# FormulaCore.net
KiCad netlist of a schematic drawn in EAGLE
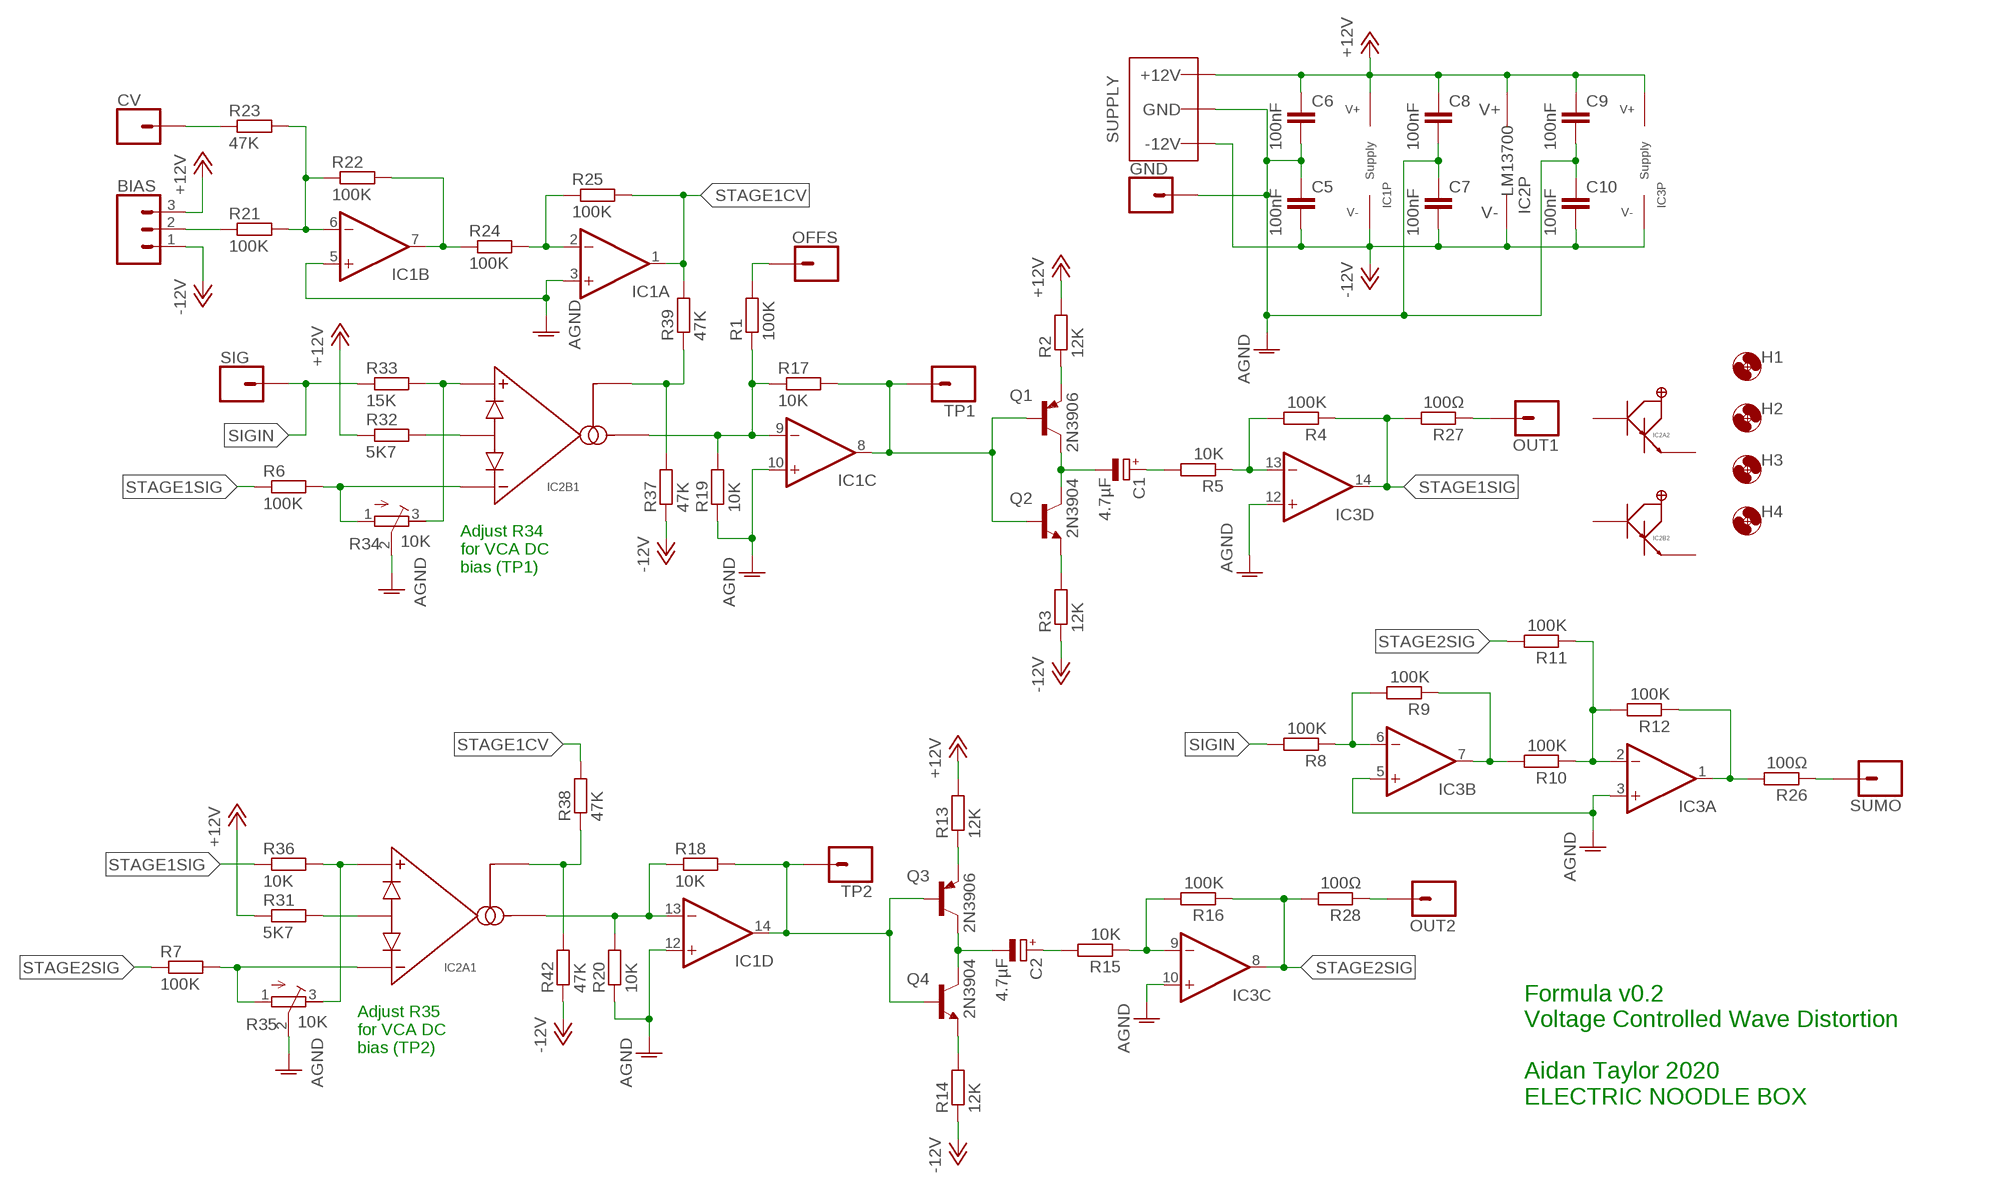
[diagram p0: schematic, sheet 1]

(export (version "E")
  (design (tool "Eeschema 10.0.6"))
  (components
    (comp (ref "BIAS")
      (value "3XWIREPAD")
      (footprint "eagle-import:1X03")
      (libsource (lib "eagle-import") (part "3XWIREPAD"))
    )
    (comp (ref "C1")
      (value "4.7µF")
      (footprint "eagle-import:E2,5-5")
      (libsource (lib "eagle-import") (part "CPOL-EUE2.5-5"))
    )
    (comp (ref "C2")
      (value "4.7µF")
      (footprint "eagle-import:E2,5-5")
      (libsource (lib "eagle-import") (part "CPOL-EUE2.5-5"))
    )
    (comp (ref "C5")
      (value "100nF")
      (footprint "eagle-import:C050-025X075")
      (libsource (lib "eagle-import") (part "C-EU050-025X075"))
    )
    (comp (ref "C6")
      (value "100nF")
      (footprint "eagle-import:C050-025X075")
      (libsource (lib "eagle-import") (part "C-EU050-025X075"))
    )
    (comp (ref "C7")
      (value "100nF")
      (footprint "eagle-import:C050-025X075")
      (libsource (lib "eagle-import") (part "C-EU050-025X075"))
    )
    (comp (ref "C8")
      (value "100nF")
      (footprint "eagle-import:C050-025X075")
      (libsource (lib "eagle-import") (part "C-EU050-025X075"))
    )
    (comp (ref "C9")
      (value "100nF")
      (footprint "eagle-import:C050-025X075")
      (libsource (lib "eagle-import") (part "C-EU050-025X075"))
    )
    (comp (ref "C10")
      (value "100nF")
      (footprint "eagle-import:C050-025X075")
      (libsource (lib "eagle-import") (part "C-EU050-025X075"))
    )
    (comp (ref "CV")
      (value "1XWIREPAD")
      (footprint "eagle-import:1X01")
      (libsource (lib "eagle-import") (part "1XWIREPAD"))
    )
    (comp (ref "GND")
      (value "1XWIREPAD")
      (footprint "eagle-import:1X01")
      (libsource (lib "eagle-import") (part "1XWIREPAD"))
    )
    (comp (ref "H1")
      (value "MOUNT-HOLE3.2")
      (footprint "eagle-import:3,2")
      (libsource (lib "eagle-import") (part "MOUNT-HOLE3.2"))
    )
    (comp (ref "H2")
      (value "MOUNT-HOLE3.2")
      (footprint "eagle-import:3,2")
      (libsource (lib "eagle-import") (part "MOUNT-HOLE3.2"))
    )
    (comp (ref "H3")
      (value "MOUNT-HOLE3.2")
      (footprint "eagle-import:3,2")
      (libsource (lib "eagle-import") (part "MOUNT-HOLE3.2"))
    )
    (comp (ref "H4")
      (value "MOUNT-HOLE3.2")
      (footprint "eagle-import:3,2")
      (libsource (lib "eagle-import") (part "MOUNT-HOLE3.2"))
    )
    (comp (ref "IC1")
      (value "TL0X4DIL")
      (footprint "eagle-import:DIL14")
      (libsource (lib "eagle-import") (part "TL0X4DIL"))
    )
    (comp (ref "IC2")
      (value "LM13700DIL")
      (footprint "eagle-import:DIL16")
      (libsource (lib "eagle-import") (part "LM13700DIL"))
    )
    (comp (ref "IC3")
      (value "TL0X4DIL")
      (footprint "eagle-import:DIL14")
      (libsource (lib "eagle-import") (part "TL0X4DIL"))
    )
    (comp (ref "OFFS")
      (value "1XWIREPAD")
      (footprint "eagle-import:1X01")
      (libsource (lib "eagle-import") (part "1XWIREPAD"))
    )
    (comp (ref "OUT1")
      (value "1XWIREPAD")
      (footprint "eagle-import:1X01")
      (libsource (lib "eagle-import") (part "1XWIREPAD"))
    )
    (comp (ref "OUT2")
      (value "1XWIREPAD")
      (footprint "eagle-import:1X01")
      (libsource (lib "eagle-import") (part "1XWIREPAD"))
    )
    (comp (ref "Q1")
      (value "2N3906")
      (footprint "eagle-import:TO92")
      (libsource (lib "eagle-import") (part "2N3906"))
    )
    (comp (ref "Q2")
      (value "2N3904")
      (footprint "eagle-import:TO92")
      (libsource (lib "eagle-import") (part "2N3904"))
    )
    (comp (ref "Q3")
      (value "2N3906")
      (footprint "eagle-import:TO92")
      (libsource (lib "eagle-import") (part "2N3906"))
    )
    (comp (ref "Q4")
      (value "2N3904")
      (footprint "eagle-import:TO92")
      (libsource (lib "eagle-import") (part "2N3904"))
    )
    (comp (ref "R1")
      (value "100K")
      (footprint "eagle-import:0207_7")
      (libsource (lib "eagle-import") (part "R-EU_0207/7"))
    )
    (comp (ref "R2")
      (value "12K")
      (footprint "eagle-import:0207_7")
      (libsource (lib "eagle-import") (part "R-EU_0207/7"))
    )
    (comp (ref "R3")
      (value "12K")
      (footprint "eagle-import:0207_7")
      (libsource (lib "eagle-import") (part "R-EU_0207/7"))
    )
    (comp (ref "R4")
      (value "100K")
      (footprint "eagle-import:0207_7")
      (libsource (lib "eagle-import") (part "R-EU_0207/7"))
    )
    (comp (ref "R5")
      (value "10K")
      (footprint "eagle-import:0207_7")
      (libsource (lib "eagle-import") (part "R-EU_0207/7"))
    )
    (comp (ref "R6")
      (value "100K")
      (footprint "eagle-import:0207_7")
      (libsource (lib "eagle-import") (part "R-EU_0207/7"))
    )
    (comp (ref "R7")
      (value "100K")
      (footprint "eagle-import:0207_7")
      (libsource (lib "eagle-import") (part "R-EU_0207/7"))
    )
    (comp (ref "R8")
      (value "100K")
      (footprint "eagle-import:0207_7")
      (libsource (lib "eagle-import") (part "R-EU_0207/7"))
    )
    (comp (ref "R9")
      (value "100K")
      (footprint "eagle-import:0207_7")
      (libsource (lib "eagle-import") (part "R-EU_0207/7"))
    )
    (comp (ref "R10")
      (value "100K")
      (footprint "eagle-import:0207_7")
      (libsource (lib "eagle-import") (part "R-EU_0207/7"))
    )
    (comp (ref "R11")
      (value "100K")
      (footprint "eagle-import:0207_7")
      (libsource (lib "eagle-import") (part "R-EU_0207/7"))
    )
    (comp (ref "R12")
      (value "100K")
      (footprint "eagle-import:0207_7")
      (libsource (lib "eagle-import") (part "R-EU_0207/7"))
    )
    (comp (ref "R13")
      (value "12K")
      (footprint "eagle-import:0207_7")
      (libsource (lib "eagle-import") (part "R-EU_0207/7"))
    )
    (comp (ref "R14")
      (value "12K")
      (footprint "eagle-import:0207_7")
      (libsource (lib "eagle-import") (part "R-EU_0207/7"))
    )
    (comp (ref "R15")
      (value "10K")
      (footprint "eagle-import:0207_7")
      (libsource (lib "eagle-import") (part "R-EU_0207/7"))
    )
    (comp (ref "R16")
      (value "100K")
      (footprint "eagle-import:0207_7")
      (libsource (lib "eagle-import") (part "R-EU_0207/7"))
    )
    (comp (ref "R17")
      (value "10K")
      (footprint "eagle-import:0207_7")
      (libsource (lib "eagle-import") (part "R-EU_0207/7"))
    )
    (comp (ref "R18")
      (value "10K")
      (footprint "eagle-import:0207_7")
      (libsource (lib "eagle-import") (part "R-EU_0207/7"))
    )
    (comp (ref "R19")
      (value "10K")
      (footprint "eagle-import:0207_7")
      (libsource (lib "eagle-import") (part "R-EU_0207/7"))
    )
    (comp (ref "R20")
      (value "10K")
      (footprint "eagle-import:0207_7")
      (libsource (lib "eagle-import") (part "R-EU_0207/7"))
    )
    (comp (ref "R21")
      (value "100K")
      (footprint "eagle-import:0207_7")
      (libsource (lib "eagle-import") (part "R-EU_0207/7"))
    )
    (comp (ref "R22")
      (value "100K")
      (footprint "eagle-import:0207_7")
      (libsource (lib "eagle-import") (part "R-EU_0207/7"))
    )
    (comp (ref "R23")
      (value "47K")
      (footprint "eagle-import:0207_7")
      (libsource (lib "eagle-import") (part "R-EU_0207/7"))
    )
    (comp (ref "R24")
      (value "100K")
      (footprint "eagle-import:0207_7")
      (libsource (lib "eagle-import") (part "R-EU_0207/7"))
    )
    (comp (ref "R25")
      (value "100K")
      (footprint "eagle-import:0207_7")
      (libsource (lib "eagle-import") (part "R-EU_0207/7"))
    )
    (comp (ref "R26")
      (value "100Ω")
      (footprint "eagle-import:0207_7")
      (libsource (lib "eagle-import") (part "R-EU_0207/7"))
    )
    (comp (ref "R27")
      (value "100Ω")
      (footprint "eagle-import:0207_7")
      (libsource (lib "eagle-import") (part "R-EU_0207/7"))
    )
    (comp (ref "R28")
      (value "100Ω")
      (footprint "eagle-import:0207_7")
      (libsource (lib "eagle-import") (part "R-EU_0207/7"))
    )
    (comp (ref "R31")
      (value "5K7")
      (footprint "eagle-import:0207_7")
      (libsource (lib "eagle-import") (part "R-EU_0207/7"))
    )
    (comp (ref "R32")
      (value "5K7")
      (footprint "eagle-import:0207_7")
      (libsource (lib "eagle-import") (part "R-EU_0207/7"))
    )
    (comp (ref "R33")
      (value "15K")
      (footprint "eagle-import:0207_7")
      (libsource (lib "eagle-import") (part "R-EU_0207/7"))
    )
    (comp (ref "R34")
      (value "10K")
      (footprint "eagle-import:RTRIM3296W")
      (libsource (lib "eagle-import") (part "R-TRIMM3296W"))
    )
    (comp (ref "R35")
      (value "10K")
      (footprint "eagle-import:RTRIM3296W")
      (libsource (lib "eagle-import") (part "R-TRIMM3296W"))
    )
    (comp (ref "R36")
      (value "10K")
      (footprint "eagle-import:0207_7")
      (libsource (lib "eagle-import") (part "R-EU_0207/7"))
    )
    (comp (ref "R37")
      (value "47K")
      (footprint "eagle-import:0207_7")
      (libsource (lib "eagle-import") (part "R-EU_0207/7"))
    )
    (comp (ref "R38")
      (value "47K")
      (footprint "eagle-import:0207_7")
      (libsource (lib "eagle-import") (part "R-EU_0207/7"))
    )
    (comp (ref "R39")
      (value "47K")
      (footprint "eagle-import:0207_7")
      (libsource (lib "eagle-import") (part "R-EU_0207/7"))
    )
    (comp (ref "R42")
      (value "47K")
      (footprint "eagle-import:0207_7")
      (libsource (lib "eagle-import") (part "R-EU_0207/7"))
    )
    (comp (ref "SIG")
      (value "1XWIREPAD")
      (footprint "eagle-import:1X01")
      (libsource (lib "eagle-import") (part "1XWIREPAD"))
    )
    (comp (ref "SUMO")
      (value "1XWIREPAD")
      (footprint "eagle-import:1X01")
      (libsource (lib "eagle-import") (part "1XWIREPAD"))
    )
    (comp (ref "TP1")
      (value "1XWIREPAD")
      (footprint "eagle-import:1X01")
      (libsource (lib "eagle-import") (part "1XWIREPAD"))
    )
    (comp (ref "TP2")
      (value "1XWIREPAD")
      (footprint "eagle-import:1X01")
      (libsource (lib "eagle-import") (part "1XWIREPAD"))
    )
    (comp (ref "WP1")
      (value "COMBO_SUPPLY_HEADER")
      (footprint "eagle-import:COMBINED_POWER")
      (libsource (lib "eagle-import") (part "COMBO_SUPPLY_HEADER"))
    )
  )
  (nets
    (net (code "1") (name "+12V") (class "Default")
      (node (ref "BIAS") (pin "3") (pinfunction "3_3") (pintype "passive"))
      (node (ref "C6") (pin "1") (pinfunction "1_1") (pintype "passive"))
      (node (ref "C8") (pin "1") (pinfunction "1_1") (pintype "passive"))
      (node (ref "C9") (pin "1") (pinfunction "1_1") (pintype "passive"))
      (node (ref "IC1") (pin "4") (pinfunction "V+_4") (pintype "bidirectional"))
      (node (ref "IC2") (pin "11") (pinfunction "V+_11") (pintype "power_in"))
      (node (ref "IC3") (pin "4") (pinfunction "V+_4") (pintype "bidirectional"))
      (node (ref "R13") (pin "2") (pinfunction "2_2") (pintype "passive"))
      (node (ref "R2") (pin "2") (pinfunction "2_2") (pintype "passive"))
      (node (ref "R31") (pin "1") (pinfunction "1_1") (pintype "passive"))
      (node (ref "R32") (pin "1") (pinfunction "1_1") (pintype "passive"))
      (node (ref "WP1") (pin "V+1") (pinfunction "V++_V+1") (pintype "power_in"))
      (node (ref "WP1") (pin "V+2") (pinfunction "V++_V+2") (pintype "power_in"))
      (node (ref "WP1") (pin "V+3") (pinfunction "V++_V+3") (pintype "power_in"))
    )
    (net (code "2") (name "-12V") (class "Default")
      (node (ref "BIAS") (pin "1") (pinfunction "1_1") (pintype "passive"))
      (node (ref "C10") (pin "2") (pinfunction "2_2") (pintype "passive"))
      (node (ref "C5") (pin "2") (pinfunction "2_2") (pintype "passive"))
      (node (ref "C7") (pin "2") (pinfunction "2_2") (pintype "passive"))
      (node (ref "IC1") (pin "11") (pinfunction "V-_11") (pintype "bidirectional"))
      (node (ref "IC2") (pin "6") (pinfunction "V-_6") (pintype "power_in"))
      (node (ref "IC3") (pin "11") (pinfunction "V-_11") (pintype "bidirectional"))
      (node (ref "R14") (pin "1") (pinfunction "1_1") (pintype "passive"))
      (node (ref "R3") (pin "1") (pinfunction "1_1") (pintype "passive"))
      (node (ref "R37") (pin "1") (pinfunction "1_1") (pintype "passive"))
      (node (ref "R42") (pin "1") (pinfunction "1_1") (pintype "passive"))
      (node (ref "WP1") (pin "V-1") (pinfunction "V--_V-1") (pintype "power_in"))
      (node (ref "WP1") (pin "V-2") (pinfunction "V--_V-2") (pintype "power_in"))
      (node (ref "WP1") (pin "V-3") (pinfunction "V--_V-3") (pintype "power_in"))
    )
    (net (code "3") (name "AGND") (class "Default")
      (node (ref "C10") (pin "1") (pinfunction "1_1") (pintype "passive"))
      (node (ref "C5") (pin "1") (pinfunction "1_1") (pintype "passive"))
      (node (ref "C6") (pin "2") (pinfunction "2_2") (pintype "passive"))
      (node (ref "C7") (pin "1") (pinfunction "1_1") (pintype "passive"))
      (node (ref "C8") (pin "2") (pinfunction "2_2") (pintype "passive"))
      (node (ref "C9") (pin "2") (pinfunction "2_2") (pintype "passive"))
      (node (ref "GND") (pin "1") (pinfunction "1_1") (pintype "passive"))
      (node (ref "IC1") (pin "10") (pinfunction "+IN_10") (pintype "input"))
      (node (ref "IC1") (pin "12") (pinfunction "+IN_12") (pintype "input"))
      (node (ref "IC1") (pin "3") (pinfunction "+IN_3") (pintype "input"))
      (node (ref "IC1") (pin "5") (pinfunction "+IN_5") (pintype "input"))
      (node (ref "IC3") (pin "10") (pinfunction "+IN_10") (pintype "input"))
      (node (ref "IC3") (pin "12") (pinfunction "+IN_12") (pintype "input"))
      (node (ref "IC3") (pin "3") (pinfunction "+IN_3") (pintype "input"))
      (node (ref "IC3") (pin "5") (pinfunction "+IN_5") (pintype "input"))
      (node (ref "R19") (pin "1") (pinfunction "1_1") (pintype "passive"))
      (node (ref "R20") (pin "1") (pinfunction "1_1") (pintype "passive"))
      (node (ref "R34") (pin "2") (pinfunction "S_2") (pintype "passive"))
      (node (ref "R35") (pin "2") (pinfunction "S_2") (pintype "passive"))
      (node (ref "WP1") (pin "GND1") (pinfunction "AGND_GND1") (pintype "power_in"))
      (node (ref "WP1") (pin "GND2") (pinfunction "AGND_GND2") (pintype "power_in"))
      (node (ref "WP1") (pin "GND3") (pinfunction "AGND_GND3") (pintype "power_in"))
      (node (ref "WP1") (pin "GND4") (pinfunction "AGND_GND4") (pintype "power_in"))
      (node (ref "WP1") (pin "GND5") (pinfunction "AGND_GND5") (pintype "power_in"))
      (node (ref "WP1") (pin "GND6") (pinfunction "AGND_GND6") (pintype "power_in"))
      (node (ref "WP1") (pin "GND7") (pinfunction "AGND_GND7") (pintype "power_in"))
      (node (ref "WP1") (pin "GND8") (pinfunction "AGND_GND8") (pintype "power_in"))
    )
    (net (code "4") (name "Net-(BIAS-Pad2)") (class "Default")
      (node (ref "BIAS") (pin "2") (pinfunction "2_2") (pintype "passive"))
      (node (ref "R21") (pin "1") (pinfunction "1_1") (pintype "passive"))
    )
    (net (code "5") (name "Net-(C1-Pad+)") (class "Default")
      (node (ref "C1") (pin "+") (pinfunction "+_+") (pintype "passive"))
      (node (ref "R5") (pin "2") (pinfunction "2_2") (pintype "passive"))
    )
    (net (code "6") (name "Net-(C2-Pad+)") (class "Default")
      (node (ref "C2") (pin "+") (pinfunction "+_+") (pintype "passive"))
      (node (ref "R15") (pin "2") (pinfunction "2_2") (pintype "passive"))
    )
    (net (code "7") (name "Net-(CV-Pad1)") (class "Default")
      (node (ref "CV") (pin "1") (pinfunction "1_1") (pintype "passive"))
      (node (ref "R23") (pin "1") (pinfunction "1_1") (pintype "passive"))
    )
    (net (code "8") (name "Net-(IC1A--IN)") (class "Default")
      (node (ref "IC1") (pin "2") (pinfunction "-IN_2") (pintype "input"))
      (node (ref "R24") (pin "2") (pinfunction "2_2") (pintype "passive"))
      (node (ref "R25") (pin "1") (pinfunction "1_1") (pintype "passive"))
    )
    (net (code "9") (name "Net-(IC1B--IN)") (class "Default")
      (node (ref "IC1") (pin "6") (pinfunction "-IN_6") (pintype "input"))
      (node (ref "R21") (pin "2") (pinfunction "2_2") (pintype "passive"))
      (node (ref "R22") (pin "1") (pinfunction "1_1") (pintype "passive"))
      (node (ref "R23") (pin "2") (pinfunction "2_2") (pintype "passive"))
    )
    (net (code "10") (name "Net-(IC1B-OUT)") (class "Default")
      (node (ref "IC1") (pin "7") (pinfunction "OUT_7") (pintype "output"))
      (node (ref "R22") (pin "2") (pinfunction "2_2") (pintype "passive"))
      (node (ref "R24") (pin "1") (pinfunction "1_1") (pintype "passive"))
    )
    (net (code "11") (name "Net-(IC1C--IN)") (class "Default")
      (node (ref "IC1") (pin "9") (pinfunction "-IN_9") (pintype "input"))
      (node (ref "IC2") (pin "12") (pinfunction "AMPOUT_12") (pintype "output"))
      (node (ref "R1") (pin "1") (pinfunction "1_1") (pintype "passive"))
      (node (ref "R17") (pin "1") (pinfunction "1_1") (pintype "passive"))
      (node (ref "R19") (pin "2") (pinfunction "2_2") (pintype "passive"))
    )
    (net (code "12") (name "Net-(IC1C-OUT)") (class "Default")
      (node (ref "IC1") (pin "8") (pinfunction "OUT_8") (pintype "output"))
      (node (ref "Q1") (pin "2") (pinfunction "B_2") (pintype "passive"))
      (node (ref "Q2") (pin "2") (pinfunction "B_2") (pintype "passive"))
      (node (ref "R17") (pin "2") (pinfunction "2_2") (pintype "passive"))
      (node (ref "TP1") (pin "1") (pinfunction "1_1") (pintype "passive"))
    )
    (net (code "13") (name "Net-(IC1D--IN)") (class "Default")
      (node (ref "IC1") (pin "13") (pinfunction "-IN_13") (pintype "input"))
      (node (ref "IC2") (pin "5") (pinfunction "AMPOUT_5") (pintype "output"))
      (node (ref "R18") (pin "1") (pinfunction "1_1") (pintype "passive"))
      (node (ref "R20") (pin "2") (pinfunction "2_2") (pintype "passive"))
    )
    (net (code "14") (name "Net-(IC1D-OUT)") (class "Default")
      (node (ref "IC1") (pin "14") (pinfunction "OUT_14") (pintype "output"))
      (node (ref "Q3") (pin "2") (pinfunction "B_2") (pintype "passive"))
      (node (ref "Q4") (pin "2") (pinfunction "B_2") (pintype "passive"))
      (node (ref "R18") (pin "2") (pinfunction "2_2") (pintype "passive"))
      (node (ref "TP2") (pin "1") (pinfunction "1_1") (pintype "passive"))
    )
    (net (code "15") (name "Net-(IC2A-AMP+)") (class "Default")
      (node (ref "IC2") (pin "3") (pinfunction "AMP+_3") (pintype "input"))
      (node (ref "R35") (pin "3") (pinfunction "E_3") (pintype "passive"))
      (node (ref "R36") (pin "2") (pinfunction "2_2") (pintype "passive"))
    )
    (net (code "16") (name "Net-(IC2A-AMP-)") (class "Default")
      (node (ref "IC2") (pin "4") (pinfunction "AMP-_4") (pintype "input"))
      (node (ref "R35") (pin "1") (pinfunction "A_1") (pintype "passive"))
      (node (ref "R7") (pin "2") (pinfunction "2_2") (pintype "passive"))
    )
    (net (code "17") (name "Net-(IC2A-AMPBIAS)") (class "Default")
      (node (ref "IC2") (pin "1") (pinfunction "AMPBIAS_1") (pintype "input"))
      (node (ref "R38") (pin "1") (pinfunction "1_1") (pintype "passive"))
      (node (ref "R42") (pin "2") (pinfunction "2_2") (pintype "passive"))
    )
    (net (code "18") (name "Net-(IC2A-DIODES)") (class "Default")
      (node (ref "IC2") (pin "2") (pinfunction "DIODES_2") (pintype "input"))
      (node (ref "R31") (pin "2") (pinfunction "2_2") (pintype "passive"))
    )
    (net (code "19") (name "Net-(IC2C-AMP+)") (class "Default")
      (node (ref "IC2") (pin "14") (pinfunction "AMP+_14") (pintype "input"))
      (node (ref "R33") (pin "2") (pinfunction "2_2") (pintype "passive"))
      (node (ref "R34") (pin "3") (pinfunction "E_3") (pintype "passive"))
    )
    (net (code "20") (name "Net-(IC2C-AMP-)") (class "Default")
      (node (ref "IC2") (pin "13") (pinfunction "AMP-_13") (pintype "input"))
      (node (ref "R34") (pin "1") (pinfunction "A_1") (pintype "passive"))
      (node (ref "R6") (pin "2") (pinfunction "2_2") (pintype "passive"))
    )
    (net (code "21") (name "Net-(IC2C-AMPBIAS)") (class "Default")
      (node (ref "IC2") (pin "16") (pinfunction "AMPBIAS_16") (pintype "input"))
      (node (ref "R37") (pin "2") (pinfunction "2_2") (pintype "passive"))
      (node (ref "R39") (pin "1") (pinfunction "1_1") (pintype "passive"))
    )
    (net (code "22") (name "Net-(IC2C-DIODES)") (class "Default")
      (node (ref "IC2") (pin "15") (pinfunction "DIODES_15") (pintype "input"))
      (node (ref "R32") (pin "2") (pinfunction "2_2") (pintype "passive"))
    )
    (net (code "23") (name "Net-(IC3A--IN)") (class "Default")
      (node (ref "IC3") (pin "2") (pinfunction "-IN_2") (pintype "input"))
      (node (ref "R10") (pin "1") (pinfunction "1_1") (pintype "passive"))
      (node (ref "R11") (pin "1") (pinfunction "1_1") (pintype "passive"))
      (node (ref "R12") (pin "2") (pinfunction "2_2") (pintype "passive"))
    )
    (net (code "24") (name "Net-(IC3A-OUT)") (class "Default")
      (node (ref "IC3") (pin "1") (pinfunction "OUT_1") (pintype "output"))
      (node (ref "R12") (pin "1") (pinfunction "1_1") (pintype "passive"))
      (node (ref "R26") (pin "2") (pinfunction "2_2") (pintype "passive"))
    )
    (net (code "25") (name "Net-(IC3B--IN)") (class "Default")
      (node (ref "IC3") (pin "6") (pinfunction "-IN_6") (pintype "input"))
      (node (ref "R8") (pin "1") (pinfunction "1_1") (pintype "passive"))
      (node (ref "R9") (pin "2") (pinfunction "2_2") (pintype "passive"))
    )
    (net (code "26") (name "Net-(IC3B-OUT)") (class "Default")
      (node (ref "IC3") (pin "7") (pinfunction "OUT_7") (pintype "output"))
      (node (ref "R10") (pin "2") (pinfunction "2_2") (pintype "passive"))
      (node (ref "R9") (pin "1") (pinfunction "1_1") (pintype "passive"))
    )
    (net (code "27") (name "Net-(IC3C--IN)") (class "Default")
      (node (ref "IC3") (pin "9") (pinfunction "-IN_9") (pintype "input"))
      (node (ref "R15") (pin "1") (pinfunction "1_1") (pintype "passive"))
      (node (ref "R16") (pin "2") (pinfunction "2_2") (pintype "passive"))
    )
    (net (code "28") (name "Net-(IC3D--IN)") (class "Default")
      (node (ref "IC3") (pin "13") (pinfunction "-IN_13") (pintype "input"))
      (node (ref "R4") (pin "2") (pinfunction "2_2") (pintype "passive"))
      (node (ref "R5") (pin "1") (pinfunction "1_1") (pintype "passive"))
    )
    (net (code "29") (name "Net-(OFFS-Pad1)") (class "Default")
      (node (ref "OFFS") (pin "1") (pinfunction "1_1") (pintype "passive"))
      (node (ref "R1") (pin "2") (pinfunction "2_2") (pintype "passive"))
    )
    (net (code "30") (name "Net-(OUT1-Pad1)") (class "Default")
      (node (ref "OUT1") (pin "1") (pinfunction "1_1") (pintype "passive"))
      (node (ref "R27") (pin "1") (pinfunction "1_1") (pintype "passive"))
    )
    (net (code "31") (name "Net-(OUT2-Pad1)") (class "Default")
      (node (ref "OUT2") (pin "1") (pinfunction "1_1") (pintype "passive"))
      (node (ref "R28") (pin "1") (pinfunction "1_1") (pintype "passive"))
    )
    (net (code "32") (name "Net-(Q1-C)") (class "Default")
      (node (ref "C1") (pin "-") (pinfunction "-_-") (pintype "passive"))
      (node (ref "Q1") (pin "1") (pinfunction "C_1") (pintype "passive"))
      (node (ref "Q2") (pin "1") (pinfunction "C_1") (pintype "passive"))
    )
    (net (code "33") (name "Net-(Q1-E)") (class "Default")
      (node (ref "Q1") (pin "3") (pinfunction "E_3") (pintype "passive"))
      (node (ref "R2") (pin "1") (pinfunction "1_1") (pintype "passive"))
    )
    (net (code "34") (name "Net-(Q2-E)") (class "Default")
      (node (ref "Q2") (pin "3") (pinfunction "E_3") (pintype "passive"))
      (node (ref "R3") (pin "2") (pinfunction "2_2") (pintype "passive"))
    )
    (net (code "35") (name "Net-(Q3-C)") (class "Default")
      (node (ref "C2") (pin "-") (pinfunction "-_-") (pintype "passive"))
      (node (ref "Q3") (pin "1") (pinfunction "C_1") (pintype "passive"))
      (node (ref "Q4") (pin "1") (pinfunction "C_1") (pintype "passive"))
    )
    (net (code "36") (name "Net-(Q3-E)") (class "Default")
      (node (ref "Q3") (pin "3") (pinfunction "E_3") (pintype "passive"))
      (node (ref "R13") (pin "1") (pinfunction "1_1") (pintype "passive"))
    )
    (net (code "37") (name "Net-(Q4-E)") (class "Default")
      (node (ref "Q4") (pin "3") (pinfunction "E_3") (pintype "passive"))
      (node (ref "R14") (pin "2") (pinfunction "2_2") (pintype "passive"))
    )
    (net (code "38") (name "Net-(R26-Pad1)") (class "Default")
      (node (ref "R26") (pin "1") (pinfunction "1_1") (pintype "passive"))
      (node (ref "SUMO") (pin "1") (pinfunction "1_1") (pintype "passive"))
    )
    (net (code "39") (name "SIGIN") (class "Default")
      (node (ref "R33") (pin "1") (pinfunction "1_1") (pintype "passive"))
      (node (ref "R8") (pin "2") (pinfunction "2_2") (pintype "passive"))
      (node (ref "SIG") (pin "1") (pinfunction "1_1") (pintype "passive"))
    )
    (net (code "40") (name "STAGE1CV") (class "Default")
      (node (ref "IC1") (pin "1") (pinfunction "OUT_1") (pintype "output"))
      (node (ref "R25") (pin "2") (pinfunction "2_2") (pintype "passive"))
      (node (ref "R38") (pin "2") (pinfunction "2_2") (pintype "passive"))
      (node (ref "R39") (pin "2") (pinfunction "2_2") (pintype "passive"))
    )
    (net (code "41") (name "STAGE1SIG") (class "Default")
      (node (ref "IC3") (pin "14") (pinfunction "OUT_14") (pintype "output"))
      (node (ref "R27") (pin "2") (pinfunction "2_2") (pintype "passive"))
      (node (ref "R36") (pin "1") (pinfunction "1_1") (pintype "passive"))
      (node (ref "R4") (pin "1") (pinfunction "1_1") (pintype "passive"))
      (node (ref "R6") (pin "1") (pinfunction "1_1") (pintype "passive"))
    )
    (net (code "42") (name "STAGE2SIG") (class "Default")
      (node (ref "IC3") (pin "8") (pinfunction "OUT_8") (pintype "output"))
      (node (ref "R11") (pin "2") (pinfunction "2_2") (pintype "passive"))
      (node (ref "R16") (pin "1") (pinfunction "1_1") (pintype "passive"))
      (node (ref "R28") (pin "2") (pinfunction "2_2") (pintype "passive"))
      (node (ref "R7") (pin "1") (pinfunction "1_1") (pintype "passive"))
    )
    (net (code "43") (name "unconnected-(IC2B-BUFF_IN-Pad7)") (class "Default")
      (node (ref "IC2") (pin "7") (pinfunction "BUFF_IN_7") (pintype "input"))
    )
    (net (code "44") (name "unconnected-(IC2B-BUFF_OUT-Pad8)") (class "Default")
      (node (ref "IC2") (pin "8") (pinfunction "BUFF_OUT_8") (pintype "bidirectional"))
    )
    (net (code "45") (name "unconnected-(IC2D-BUFF_IN-Pad10)") (class "Default")
      (node (ref "IC2") (pin "10") (pinfunction "BUFF_IN_10") (pintype "input"))
    )
    (net (code "46") (name "unconnected-(IC2D-BUFF_OUT-Pad9)") (class "Default")
      (node (ref "IC2") (pin "9") (pinfunction "BUFF_OUT_9") (pintype "bidirectional"))
    )
  )
)
